# Benchtop_Power_Supply-v13.net
KiCad netlist of a schematic drawn in EAGLE
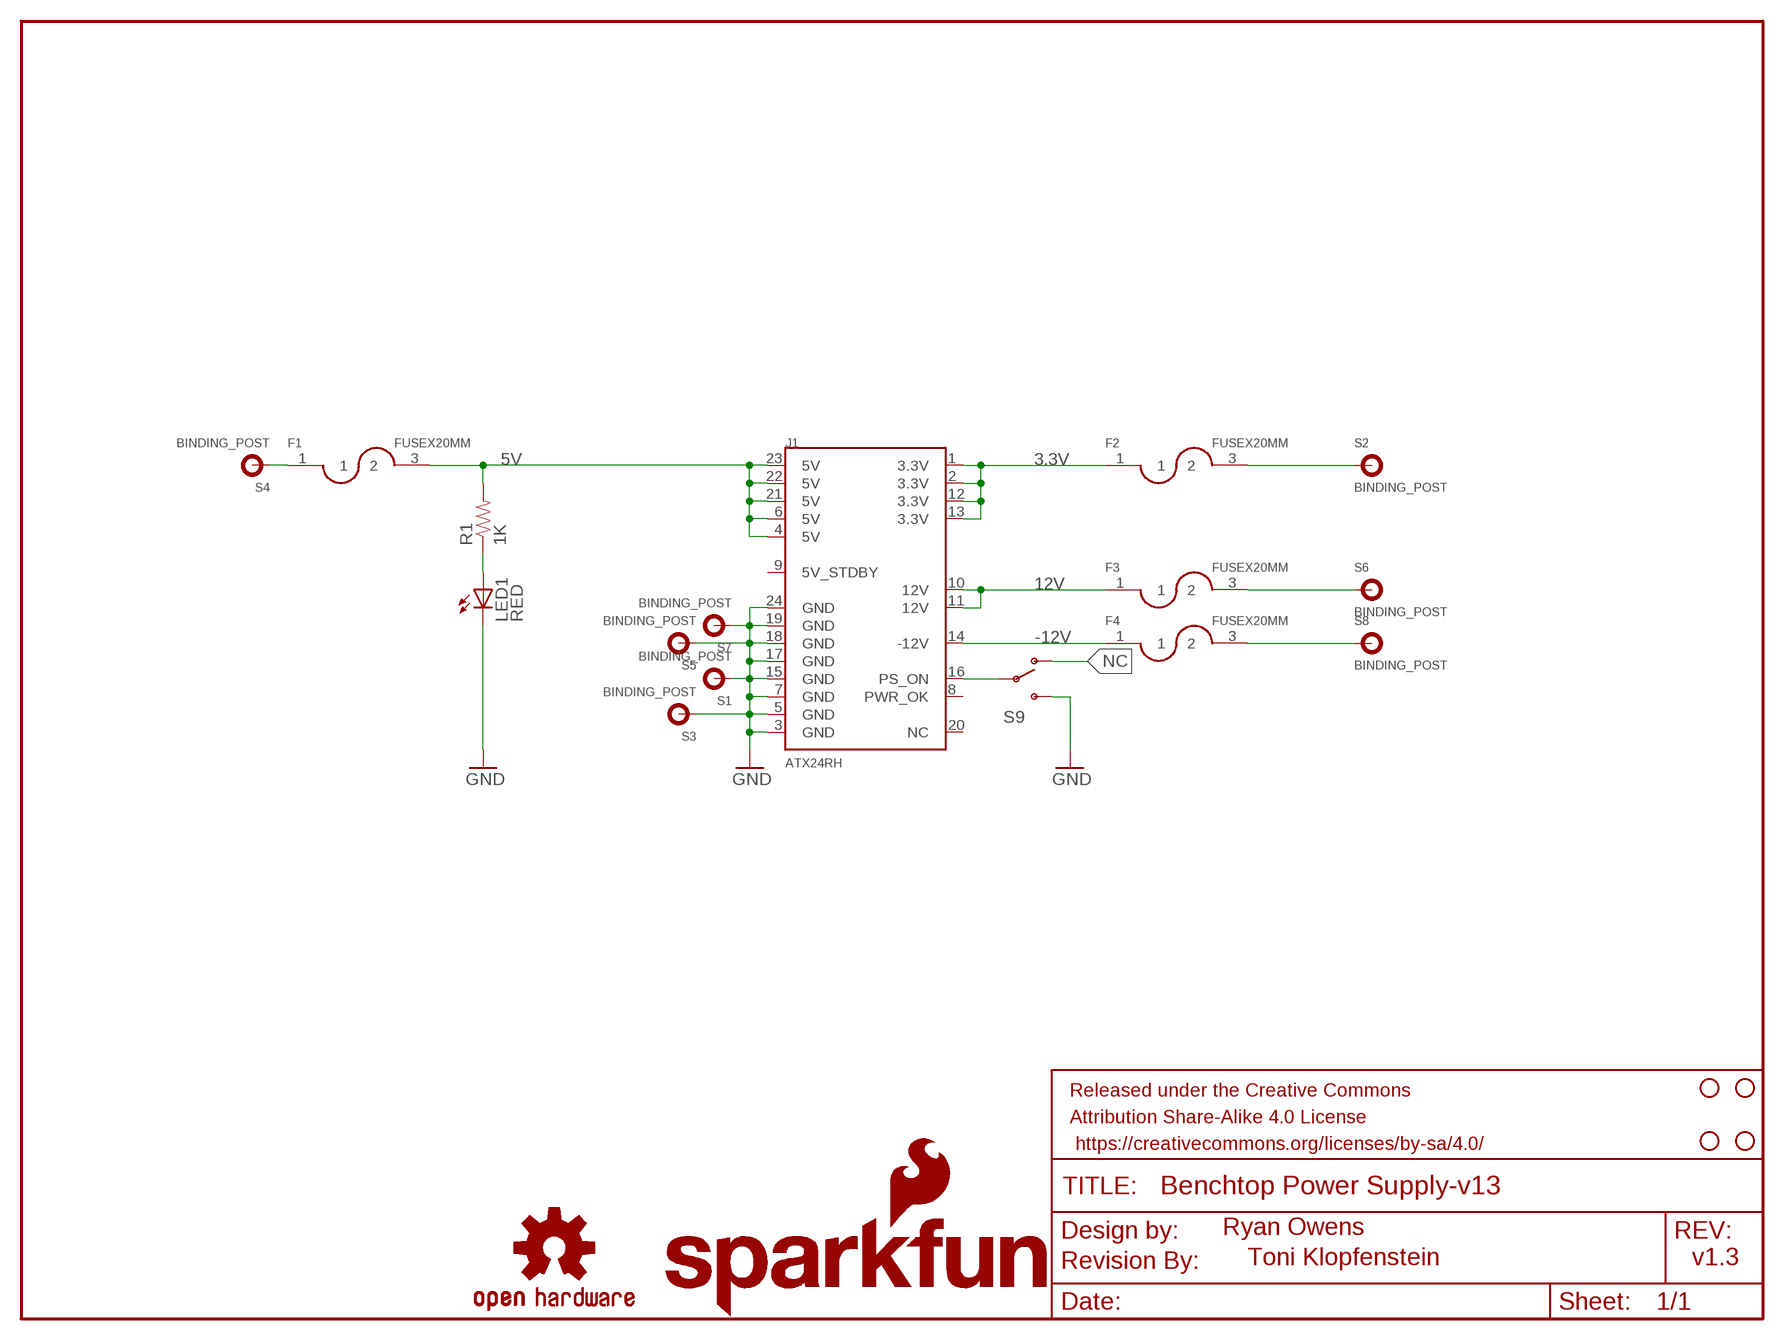
[diagram p0: schematic, sheet 1]

(export (version "E")
  (design (tool "Eeschema 10.0.6"))
  (components
    (comp (ref "F1")
      (value "FUSEX20MM")
      (footprint "eagle-import:FUSE_5MM")
      (libsource (lib "eagle-import") (part "FUSEX20MM"))
    )
    (comp (ref "F2")
      (value "FUSEX20MM")
      (footprint "eagle-import:FUSE_5MM")
      (libsource (lib "eagle-import") (part "FUSEX20MM"))
    )
    (comp (ref "F3")
      (value "FUSEX20MM")
      (footprint "eagle-import:FUSE_5MM")
      (libsource (lib "eagle-import") (part "FUSEX20MM"))
    )
    (comp (ref "F4")
      (value "FUSEX20MM")
      (footprint "eagle-import:FUSE_5MM")
      (libsource (lib "eagle-import") (part "FUSEX20MM"))
    )
    (comp (ref "FRAME1")
      (value "FRAME-LETTER")
      (footprint "eagle-import:CREATIVE_COMMONS")
      (libsource (lib "eagle-import") (part "FRAME-LETTER"))
    )
    (comp (ref "J1")
      (value "ATX24RH")
      (footprint "eagle-import:ATX24_RIGHT_ANGLE")
      (libsource (lib "eagle-import") (part "ATX24RH"))
    )
    (comp (ref "JP1")
      (value "SFE_LOGO_NAME_FLAME.3_INCH")
      (footprint "eagle-import:SFE_LOGO_NAME_FLAME_.3")
      (libsource (lib "eagle-import") (part "SFE_LOGO_NAME_FLAME.3_INCH"))
    )
    (comp (ref "JP2")
      (value "STAND-OFF")
      (footprint "eagle-import:STAND-OFF")
      (libsource (lib "eagle-import") (part "STAND-OFF"))
    )
    (comp (ref "JP3")
      (value "STAND-OFF")
      (footprint "eagle-import:STAND-OFF")
      (libsource (lib "eagle-import") (part "STAND-OFF"))
    )
    (comp (ref "JP4")
      (value "STAND-OFF")
      (footprint "eagle-import:STAND-OFF")
      (libsource (lib "eagle-import") (part "STAND-OFF"))
    )
    (comp (ref "JP5")
      (value "STAND-OFF")
      (footprint "eagle-import:STAND-OFF")
      (libsource (lib "eagle-import") (part "STAND-OFF"))
    )
    (comp (ref "LED1")
      (value "RED")
      (footprint "eagle-import:LED5MM")
      (libsource (lib "eagle-import") (part "LED5MM"))
    )
    (comp (ref "LOGO1")
      (value "OSHW-LOGOL")
      (footprint "eagle-import:OSHW-LOGO-L")
      (libsource (lib "eagle-import") (part "OSHW-LOGOL"))
    )
    (comp (ref "R1")
      (value "1K")
      (footprint "eagle-import:AXIAL-0.3")
      (libsource (lib "eagle-import") (part "RESISTORPTH1"))
    )
    (comp (ref "S1")
      (value "BINDING_POST")
      (footprint "eagle-import:BINDING_POST")
      (libsource (lib "eagle-import") (part "BINDING_POST"))
    )
    (comp (ref "S2")
      (value "BINDING_POST")
      (footprint "eagle-import:BINDING_POST")
      (libsource (lib "eagle-import") (part "BINDING_POST"))
    )
    (comp (ref "S3")
      (value "BINDING_POST")
      (footprint "eagle-import:BINDING_POST")
      (libsource (lib "eagle-import") (part "BINDING_POST"))
    )
    (comp (ref "S4")
      (value "BINDING_POST")
      (footprint "eagle-import:BINDING_POST")
      (libsource (lib "eagle-import") (part "BINDING_POST"))
    )
    (comp (ref "S5")
      (value "BINDING_POST")
      (footprint "eagle-import:BINDING_POST")
      (libsource (lib "eagle-import") (part "BINDING_POST"))
    )
    (comp (ref "S6")
      (value "BINDING_POST")
      (footprint "eagle-import:BINDING_POST")
      (libsource (lib "eagle-import") (part "BINDING_POST"))
    )
    (comp (ref "S7")
      (value "BINDING_POST")
      (footprint "eagle-import:BINDING_POST")
      (libsource (lib "eagle-import") (part "BINDING_POST"))
    )
    (comp (ref "S8")
      (value "BINDING_POST")
      (footprint "eagle-import:BINDING_POST")
      (libsource (lib "eagle-import") (part "BINDING_POST"))
    )
    (comp (ref "S9")
      (value "SWITCH-SPDTKIT")
      (footprint "eagle-import:SWITCH-SPDT_KIT")
      (libsource (lib "eagle-import") (part "SWITCH-SPDTKIT"))
    )
    (comp (ref "U$1")
      (value "REVISION")
      (footprint "eagle-import:REVISION")
      (libsource (lib "eagle-import") (part "REVISION"))
    )
  )
  (nets
    (net (code "1") (name "/-12V") (class "Default")
      (node (ref "F4") (pin "1") (pinfunction "1_1") (pintype "bidirectional"))
      (node (ref "J1") (pin "14") (pinfunction "-12V_14") (pintype "bidirectional"))
    )
    (net (code "2") (name "/3.3V") (class "Default")
      (node (ref "F2") (pin "1") (pinfunction "1_1") (pintype "bidirectional"))
      (node (ref "J1") (pin "1") (pinfunction "3.3V_1") (pintype "bidirectional"))
      (node (ref "J1") (pin "12") (pinfunction "3.3V_12") (pintype "bidirectional"))
      (node (ref "J1") (pin "13") (pinfunction "3.3V_13") (pintype "bidirectional"))
      (node (ref "J1") (pin "2") (pinfunction "3.3V_2") (pintype "bidirectional"))
    )
    (net (code "3") (name "/5V") (class "Default")
      (node (ref "F1") (pin "3") (pinfunction "2_3") (pintype "bidirectional"))
      (node (ref "J1") (pin "21") (pinfunction "5V_21") (pintype "bidirectional"))
      (node (ref "J1") (pin "22") (pinfunction "5V_22") (pintype "bidirectional"))
      (node (ref "J1") (pin "23") (pinfunction "5V_23") (pintype "bidirectional"))
      (node (ref "J1") (pin "4") (pinfunction "5V_4") (pintype "bidirectional"))
      (node (ref "J1") (pin "6") (pinfunction "5V_6") (pintype "bidirectional"))
      (node (ref "R1") (pin "P$2") (pinfunction "2_P$2") (pintype "passive"))
    )
    (net (code "4") (name "/12V") (class "Default")
      (node (ref "F3") (pin "1") (pinfunction "1_1") (pintype "bidirectional"))
      (node (ref "J1") (pin "10") (pinfunction "12V_10") (pintype "bidirectional"))
      (node (ref "J1") (pin "11") (pinfunction "12V_11") (pintype "bidirectional"))
    )
    (net (code "5") (name "GND") (class "Default")
      (node (ref "J1") (pin "15") (pinfunction "GND_15") (pintype "bidirectional"))
      (node (ref "J1") (pin "17") (pinfunction "GND_17") (pintype "bidirectional"))
      (node (ref "J1") (pin "18") (pinfunction "GND_18") (pintype "bidirectional"))
      (node (ref "J1") (pin "19") (pinfunction "GND_19") (pintype "bidirectional"))
      (node (ref "J1") (pin "24") (pinfunction "GND_24") (pintype "bidirectional"))
      (node (ref "J1") (pin "3") (pinfunction "GND_3") (pintype "bidirectional"))
      (node (ref "J1") (pin "5") (pinfunction "GND_5") (pintype "bidirectional"))
      (node (ref "J1") (pin "7") (pinfunction "GND_7") (pintype "bidirectional"))
      (node (ref "LED1") (pin "K") (pinfunction "C_K") (pintype "passive"))
      (node (ref "S1") (pin "P$1") (pinfunction "P$1_P$1") (pintype "bidirectional"))
      (node (ref "S3") (pin "P$1") (pinfunction "P$1_P$1") (pintype "bidirectional"))
      (node (ref "S5") (pin "P$1") (pinfunction "P$1_P$1") (pintype "bidirectional"))
      (node (ref "S7") (pin "P$1") (pinfunction "P$1_P$1") (pintype "bidirectional"))
      (node (ref "S9") (pin "3") (pinfunction "S_3") (pintype "passive"))
    )
    (net (code "6") (name "NC") (class "Default")
      (node (ref "S9") (pin "1") (pinfunction "O_1") (pintype "passive"))
    )
    (net (code "7") (name "Net-(F1-Pad1)") (class "Default")
      (node (ref "F1") (pin "1") (pinfunction "1_1") (pintype "bidirectional"))
      (node (ref "S4") (pin "P$1") (pinfunction "P$1_P$1") (pintype "bidirectional"))
    )
    (net (code "8") (name "Net-(F2-2)") (class "Default")
      (node (ref "F2") (pin "3") (pinfunction "2_3") (pintype "bidirectional"))
      (node (ref "S2") (pin "P$1") (pinfunction "P$1_P$1") (pintype "bidirectional"))
    )
    (net (code "9") (name "Net-(F3-2)") (class "Default")
      (node (ref "F3") (pin "3") (pinfunction "2_3") (pintype "bidirectional"))
      (node (ref "S6") (pin "P$1") (pinfunction "P$1_P$1") (pintype "bidirectional"))
    )
    (net (code "10") (name "Net-(F4-2)") (class "Default")
      (node (ref "F4") (pin "3") (pinfunction "2_3") (pintype "bidirectional"))
      (node (ref "S8") (pin "P$1") (pinfunction "P$1_P$1") (pintype "bidirectional"))
    )
    (net (code "11") (name "Net-(J1-PS_ON)") (class "Default")
      (node (ref "J1") (pin "16") (pinfunction "PS_ON_16") (pintype "bidirectional"))
      (node (ref "S9") (pin "2") (pinfunction "P_2") (pintype "passive"))
    )
    (net (code "12") (name "Net-(R1-1)") (class "Default")
      (node (ref "LED1") (pin "A") (pinfunction "A_A") (pintype "passive"))
      (node (ref "R1") (pin "P$1") (pinfunction "1_P$1") (pintype "passive"))
    )
    (net (code "13") (name "unconnected-(J1-5V_STDBY-Pad9)") (class "Default")
      (node (ref "J1") (pin "9") (pinfunction "5V_STDBY_9") (pintype "bidirectional"))
    )
    (net (code "14") (name "unconnected-(J1-NC-Pad20)") (class "Default")
      (node (ref "J1") (pin "20") (pinfunction "NC_20") (pintype "bidirectional"))
    )
    (net (code "15") (name "unconnected-(J1-PWR_OK-Pad8)") (class "Default")
      (node (ref "J1") (pin "8") (pinfunction "PWR_OK_8") (pintype "bidirectional"))
    )
  )
)
